# Nixie_Board.net
KiCad netlist of a schematic drawn in Altium Designer
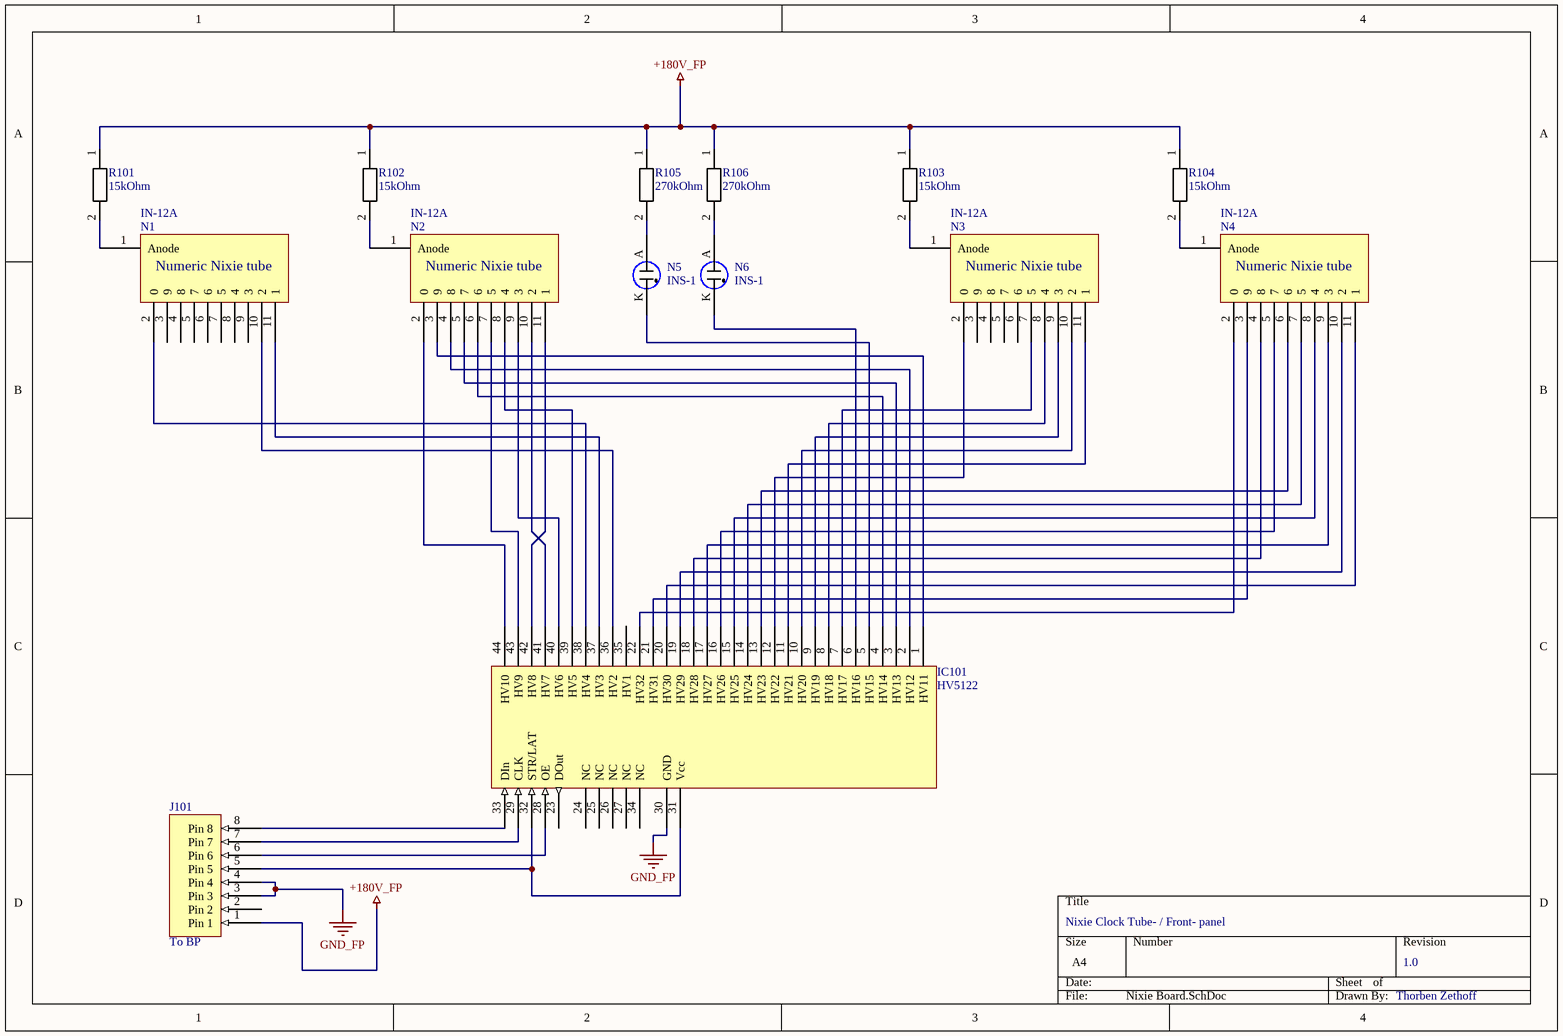
[diagram p0: Nixie Board.SchDoc]

(export (version "E")
  (design (tool "Eeschema 10.0.6"))
  (components
    (comp (ref "IC101")
      (value "HV5122")
      (footprint "PQFP44")
      (description "32bit HV shift register")
      (libsource (lib "stdLib") (part "HV5122"))
    )
    (comp (ref "J101")
      (value "To BP")
      (footprint "Molex 0528080871")
      (description "8 Pin FFC SMD staight")
      (libsource (lib "stdLib") (part "Molex 0528080871"))
    )
    (comp (ref "N1")
      (value "IN-12A")
      (footprint "IN12-A Nixie")
      (description "Nixie tube numeric without decimal point")
      (libsource (lib "stdLib") (part "Nixie numeric 0-9"))
    )
    (comp (ref "N2")
      (value "IN-12A")
      (footprint "IN12-A Nixie")
      (description "Nixie tube numeric without decimal point")
      (libsource (lib "stdLib") (part "Nixie numeric 0-9"))
    )
    (comp (ref "N3")
      (value "IN-12A")
      (footprint "IN12-A Nixie")
      (description "Nixie tube numeric without decimal point")
      (libsource (lib "stdLib") (part "Nixie numeric 0-9"))
    )
    (comp (ref "N4")
      (value "IN-12A")
      (footprint "IN12-A Nixie")
      (description "Nixie tube numeric without decimal point")
      (libsource (lib "stdLib") (part "Nixie numeric 0-9"))
    )
    (comp (ref "N5")
      (value "INS-1")
      (footprint "INS-1")
      (description "Neon dot indicator")
      (libsource (lib "stdLib") (part "Nixie Dot"))
    )
    (comp (ref "N6")
      (value "INS-1")
      (footprint "INS-1")
      (description "Neon dot indicator")
      (libsource (lib "stdLib") (part "Nixie Dot"))
    )
    (comp (ref "R101") (value "15kOhm") (footprint "1206") (libsource (lib "stdLib") (part "Resistor")))
    (comp (ref "R102") (value "15kOhm") (footprint "1206") (libsource (lib "stdLib") (part "Resistor")))
    (comp (ref "R103") (value "15kOhm") (footprint "1206") (libsource (lib "stdLib") (part "Resistor")))
    (comp (ref "R104") (value "15kOhm") (footprint "1206") (libsource (lib "stdLib") (part "Resistor")))
    (comp (ref "R105") (value "270kOhm") (footprint "1206") (libsource (lib "stdLib") (part "Resistor")))
    (comp (ref "R106") (value "270kOhm") (footprint "1206") (libsource (lib "stdLib") (part "Resistor")))
  )
  (nets
    (net (code "1") (name "+180V_FP") (class "Default")
      (node (ref "J101") (pin "1") (pinfunction "Pin_1_1") (pintype "input"))
      (node (ref "R101") (pin "1") (pintype "passive"))
      (node (ref "R102") (pin "1") (pintype "passive"))
      (node (ref "R103") (pin "1") (pintype "passive"))
      (node (ref "R104") (pin "1") (pintype "passive"))
      (node (ref "R105") (pin "1") (pintype "passive"))
      (node (ref "R106") (pin "1") (pintype "passive"))
    )
    (net (code "2") (name "GND_FP") (class "Default")
      (node (ref "IC101") (pin "30") (pinfunction "GND_30") (pintype "power_in"))
      (node (ref "J101") (pin "3") (pinfunction "Pin_3_3") (pintype "input"))
      (node (ref "J101") (pin "4") (pinfunction "Pin_4_4") (pintype "input"))
    )
    (net (code "3") (name "Net-(IC101-CLK)") (class "Default")
      (node (ref "IC101") (pin "29") (pinfunction "CLK_29") (pintype "input"))
      (node (ref "J101") (pin "7") (pinfunction "Pin_7_7") (pintype "input"))
    )
    (net (code "4") (name "Net-(IC101-DIn)") (class "Default")
      (node (ref "IC101") (pin "33") (pinfunction "DIn_33") (pintype "input"))
      (node (ref "J101") (pin "8") (pinfunction "Pin_8_8") (pintype "input"))
    )
    (net (code "5") (name "Net-(IC101-HV2)") (class "Default")
      (node (ref "IC101") (pin "36") (pinfunction "HV2_36") (pintype "open_collector"))
      (node (ref "N1") (pin "10") (pinfunction "2_10") (pintype "power_in"))
    )
    (net (code "6") (name "Net-(IC101-HV3)") (class "Default")
      (node (ref "IC101") (pin "37") (pinfunction "HV3_37") (pintype "open_collector"))
      (node (ref "N1") (pin "11") (pinfunction "1_11") (pintype "power_in"))
    )
    (net (code "7") (name "Net-(IC101-HV4)") (class "Default")
      (node (ref "IC101") (pin "38") (pinfunction "HV4_38") (pintype "open_collector"))
      (node (ref "N1") (pin "2") (pinfunction "0_2") (pintype "power_in"))
    )
    (net (code "8") (name "Net-(IC101-HV5)") (class "Default")
      (node (ref "IC101") (pin "39") (pinfunction "HV5_39") (pintype "open_collector"))
      (node (ref "N2") (pin "8") (pinfunction "4_8") (pintype "power_in"))
    )
    (net (code "9") (name "Net-(IC101-HV6)") (class "Default")
      (node (ref "IC101") (pin "40") (pinfunction "HV6_40") (pintype "open_collector"))
      (node (ref "N2") (pin "9") (pinfunction "3_9") (pintype "power_in"))
    )
    (net (code "10") (name "Net-(IC101-HV7)") (class "Default")
      (node (ref "IC101") (pin "41") (pinfunction "HV7_41") (pintype "open_collector"))
      (node (ref "N2") (pin "10") (pinfunction "2_10") (pintype "power_in"))
    )
    (net (code "11") (name "Net-(IC101-HV8)") (class "Default")
      (node (ref "IC101") (pin "42") (pinfunction "HV8_42") (pintype "open_collector"))
      (node (ref "N2") (pin "11") (pinfunction "1_11") (pintype "power_in"))
    )
    (net (code "12") (name "Net-(IC101-HV9)") (class "Default")
      (node (ref "IC101") (pin "43") (pinfunction "HV9_43") (pintype "open_collector"))
      (node (ref "N2") (pin "7") (pinfunction "5_7") (pintype "power_in"))
    )
    (net (code "13") (name "Net-(IC101-HV10)") (class "Default")
      (node (ref "IC101") (pin "44") (pinfunction "HV10_44") (pintype "open_collector"))
      (node (ref "N2") (pin "2") (pinfunction "0_2") (pintype "power_in"))
    )
    (net (code "14") (name "Net-(IC101-HV11)") (class "Default")
      (node (ref "IC101") (pin "1") (pinfunction "HV11_1") (pintype "open_collector"))
      (node (ref "N2") (pin "3") (pinfunction "9_3") (pintype "power_in"))
    )
    (net (code "15") (name "Net-(IC101-HV12)") (class "Default")
      (node (ref "IC101") (pin "2") (pinfunction "HV12_2") (pintype "open_collector"))
      (node (ref "N2") (pin "4") (pinfunction "8_4") (pintype "power_in"))
    )
    (net (code "16") (name "Net-(IC101-HV13)") (class "Default")
      (node (ref "IC101") (pin "3") (pinfunction "HV13_3") (pintype "open_collector"))
      (node (ref "N2") (pin "5") (pinfunction "7_5") (pintype "power_in"))
    )
    (net (code "17") (name "Net-(IC101-HV14)") (class "Default")
      (node (ref "IC101") (pin "4") (pinfunction "HV14_4") (pintype "open_collector"))
      (node (ref "N2") (pin "6") (pinfunction "6_6") (pintype "power_in"))
    )
    (net (code "18") (name "Net-(IC101-HV15)") (class "Default")
      (node (ref "IC101") (pin "5") (pinfunction "HV15_5") (pintype "open_collector"))
      (node (ref "N5") (pin "K") (pinfunction "K_K") (pintype "power_in"))
    )
    (net (code "19") (name "Net-(IC101-HV16)") (class "Default")
      (node (ref "IC101") (pin "6") (pinfunction "HV16_6") (pintype "open_collector"))
      (node (ref "N6") (pin "K") (pinfunction "K_K") (pintype "power_in"))
    )
    (net (code "20") (name "Net-(IC101-HV17)") (class "Default")
      (node (ref "IC101") (pin "7") (pinfunction "HV17_7") (pintype "open_collector"))
      (node (ref "N3") (pin "7") (pinfunction "5_7") (pintype "power_in"))
    )
    (net (code "21") (name "Net-(IC101-HV18)") (class "Default")
      (node (ref "IC101") (pin "8") (pinfunction "HV18_8") (pintype "open_collector"))
      (node (ref "N3") (pin "8") (pinfunction "4_8") (pintype "power_in"))
    )
    (net (code "22") (name "Net-(IC101-HV19)") (class "Default")
      (node (ref "IC101") (pin "9") (pinfunction "HV19_9") (pintype "open_collector"))
      (node (ref "N3") (pin "9") (pinfunction "3_9") (pintype "power_in"))
    )
    (net (code "23") (name "Net-(IC101-HV20)") (class "Default")
      (node (ref "IC101") (pin "10") (pinfunction "HV20_10") (pintype "open_collector"))
      (node (ref "N3") (pin "10") (pinfunction "2_10") (pintype "power_in"))
    )
    (net (code "24") (name "Net-(IC101-HV21)") (class "Default")
      (node (ref "IC101") (pin "11") (pinfunction "HV21_11") (pintype "open_collector"))
      (node (ref "N3") (pin "11") (pinfunction "1_11") (pintype "power_in"))
    )
    (net (code "25") (name "Net-(IC101-HV22)") (class "Default")
      (node (ref "IC101") (pin "12") (pinfunction "HV22_12") (pintype "open_collector"))
      (node (ref "N3") (pin "2") (pinfunction "0_2") (pintype "power_in"))
    )
    (net (code "26") (name "Net-(IC101-HV23)") (class "Default")
      (node (ref "IC101") (pin "13") (pinfunction "HV23_13") (pintype "open_collector"))
      (node (ref "N4") (pin "6") (pinfunction "6_6") (pintype "power_in"))
    )
    (net (code "27") (name "Net-(IC101-HV24)") (class "Default")
      (node (ref "IC101") (pin "14") (pinfunction "HV24_14") (pintype "open_collector"))
      (node (ref "N4") (pin "7") (pinfunction "5_7") (pintype "power_in"))
    )
    (net (code "28") (name "Net-(IC101-HV25)") (class "Default")
      (node (ref "IC101") (pin "15") (pinfunction "HV25_15") (pintype "open_collector"))
      (node (ref "N4") (pin "8") (pinfunction "4_8") (pintype "power_in"))
    )
    (net (code "29") (name "Net-(IC101-HV26)") (class "Default")
      (node (ref "IC101") (pin "16") (pinfunction "HV26_16") (pintype "open_collector"))
      (node (ref "N4") (pin "5") (pinfunction "7_5") (pintype "power_in"))
    )
    (net (code "30") (name "Net-(IC101-HV27)") (class "Default")
      (node (ref "IC101") (pin "17") (pinfunction "HV27_17") (pintype "open_collector"))
      (node (ref "N4") (pin "9") (pinfunction "3_9") (pintype "power_in"))
    )
    (net (code "31") (name "Net-(IC101-HV28)") (class "Default")
      (node (ref "IC101") (pin "18") (pinfunction "HV28_18") (pintype "open_collector"))
      (node (ref "N4") (pin "4") (pinfunction "8_4") (pintype "power_in"))
    )
    (net (code "32") (name "Net-(IC101-HV29)") (class "Default")
      (node (ref "IC101") (pin "19") (pinfunction "HV29_19") (pintype "open_collector"))
      (node (ref "N4") (pin "10") (pinfunction "2_10") (pintype "power_in"))
    )
    (net (code "33") (name "Net-(IC101-HV30)") (class "Default")
      (node (ref "IC101") (pin "20") (pinfunction "HV30_20") (pintype "open_collector"))
      (node (ref "N4") (pin "11") (pinfunction "1_11") (pintype "power_in"))
    )
    (net (code "34") (name "Net-(IC101-HV31)") (class "Default")
      (node (ref "IC101") (pin "21") (pinfunction "HV31_21") (pintype "open_collector"))
      (node (ref "N4") (pin "3") (pinfunction "9_3") (pintype "power_in"))
    )
    (net (code "35") (name "Net-(IC101-HV32)") (class "Default")
      (node (ref "IC101") (pin "22") (pinfunction "HV32_22") (pintype "open_collector"))
      (node (ref "N4") (pin "2") (pinfunction "0_2") (pintype "power_in"))
    )
    (net (code "36") (name "Net-(IC101-OE)") (class "Default")
      (node (ref "IC101") (pin "28") (pinfunction "OE_28") (pintype "input"))
      (node (ref "J101") (pin "6") (pinfunction "Pin_6_6") (pintype "input"))
    )
    (net (code "37") (name "Net-(IC101-STR{slash}LAT)") (class "Default")
      (node (ref "IC101") (pin "31") (pinfunction "Vcc_31") (pintype "power_in"))
      (node (ref "IC101") (pin "32") (pinfunction "STR/LAT_32") (pintype "input"))
      (node (ref "J101") (pin "5") (pinfunction "Pin_5_5") (pintype "input"))
    )
    (net (code "38") (name "Net-(N1-Anode)") (class "Default")
      (node (ref "N1") (pin "1") (pinfunction "Anode_1") (pintype "power_in"))
      (node (ref "R101") (pin "2") (pintype "passive"))
    )
    (net (code "39") (name "Net-(N2-Anode)") (class "Default")
      (node (ref "N2") (pin "1") (pinfunction "Anode_1") (pintype "power_in"))
      (node (ref "R102") (pin "2") (pintype "passive"))
    )
    (net (code "40") (name "Net-(N3-Anode)") (class "Default")
      (node (ref "N3") (pin "1") (pinfunction "Anode_1") (pintype "power_in"))
      (node (ref "R103") (pin "2") (pintype "passive"))
    )
    (net (code "41") (name "Net-(N4-Anode)") (class "Default")
      (node (ref "N4") (pin "1") (pinfunction "Anode_1") (pintype "power_in"))
      (node (ref "R104") (pin "2") (pintype "passive"))
    )
    (net (code "42") (name "Net-(N5-PadA)") (class "Default")
      (node (ref "N5") (pin "A") (pinfunction "A_A") (pintype "power_in"))
      (node (ref "R105") (pin "2") (pintype "passive"))
    )
    (net (code "43") (name "Net-(N6-PadA)") (class "Default")
      (node (ref "N6") (pin "A") (pinfunction "A_A") (pintype "power_in"))
      (node (ref "R106") (pin "2") (pintype "passive"))
    )
    (net (code "44") (name "unconnected-(IC101-DOut-Pad23)") (class "Default")
      (node (ref "IC101") (pin "23") (pinfunction "DOut_23") (pintype "output"))
    )
    (net (code "45") (name "unconnected-(IC101-HV1-Pad35)") (class "Default")
      (node (ref "IC101") (pin "35") (pinfunction "HV1_35") (pintype "open_collector"))
    )
    (net (code "46") (name "unconnected-(IC101-NC-Pad24)") (class "Default")
      (node (ref "IC101") (pin "24") (pinfunction "NC_24") (pintype "passive"))
    )
    (net (code "47") (name "unconnected-(IC101-NC-Pad25)") (class "Default")
      (node (ref "IC101") (pin "25") (pinfunction "NC_25") (pintype "passive"))
    )
    (net (code "48") (name "unconnected-(IC101-NC-Pad26)") (class "Default")
      (node (ref "IC101") (pin "26") (pinfunction "NC_26") (pintype "passive"))
    )
    (net (code "49") (name "unconnected-(IC101-NC-Pad27)") (class "Default")
      (node (ref "IC101") (pin "27") (pinfunction "NC_27") (pintype "passive"))
    )
    (net (code "50") (name "unconnected-(IC101-NC-Pad34)") (class "Default")
      (node (ref "IC101") (pin "34") (pinfunction "NC_34") (pintype "passive"))
    )
    (net (code "51") (name "unconnected-(J101-Pin_2-Pad2)") (class "Default")
      (node (ref "J101") (pin "2") (pinfunction "Pin_2_2") (pintype "input"))
    )
    (net (code "52") (name "unconnected-(N1-3-Pad9)") (class "Default")
      (node (ref "N1") (pin "9") (pinfunction "3_9") (pintype "power_in"))
    )
    (net (code "53") (name "unconnected-(N1-4-Pad8)") (class "Default")
      (node (ref "N1") (pin "8") (pinfunction "4_8") (pintype "power_in"))
    )
    (net (code "54") (name "unconnected-(N1-5-Pad7)") (class "Default")
      (node (ref "N1") (pin "7") (pinfunction "5_7") (pintype "power_in"))
    )
    (net (code "55") (name "unconnected-(N1-7-Pad5)") (class "Default")
      (node (ref "N1") (pin "5") (pinfunction "7_5") (pintype "power_in"))
    )
    (net (code "56") (name "unconnected-(N1-8-Pad4)") (class "Default")
      (node (ref "N1") (pin "4") (pinfunction "8_4") (pintype "power_in"))
    )
    (net (code "57") (name "unconnected-(N1-9-Pad3)") (class "Default")
      (node (ref "N1") (pin "3") (pinfunction "9_3") (pintype "power_in"))
    )
    (net (code "58") (name "unconnected-(N1-Pad6)") (class "Default")
      (node (ref "N1") (pin "6") (pinfunction "6_6") (pintype "power_in"))
    )
    (net (code "59") (name "unconnected-(N3-7-Pad5)") (class "Default")
      (node (ref "N3") (pin "5") (pinfunction "7_5") (pintype "power_in"))
    )
    (net (code "60") (name "unconnected-(N3-8-Pad4)") (class "Default")
      (node (ref "N3") (pin "4") (pinfunction "8_4") (pintype "power_in"))
    )
    (net (code "61") (name "unconnected-(N3-9-Pad3)") (class "Default")
      (node (ref "N3") (pin "3") (pinfunction "9_3") (pintype "power_in"))
    )
    (net (code "62") (name "unconnected-(N3-Pad6)") (class "Default")
      (node (ref "N3") (pin "6") (pinfunction "6_6") (pintype "power_in"))
    )
  )
)
